# PSoC_PyunPyun_Mini.net
KiCad netlist of a schematic drawn in EAGLE
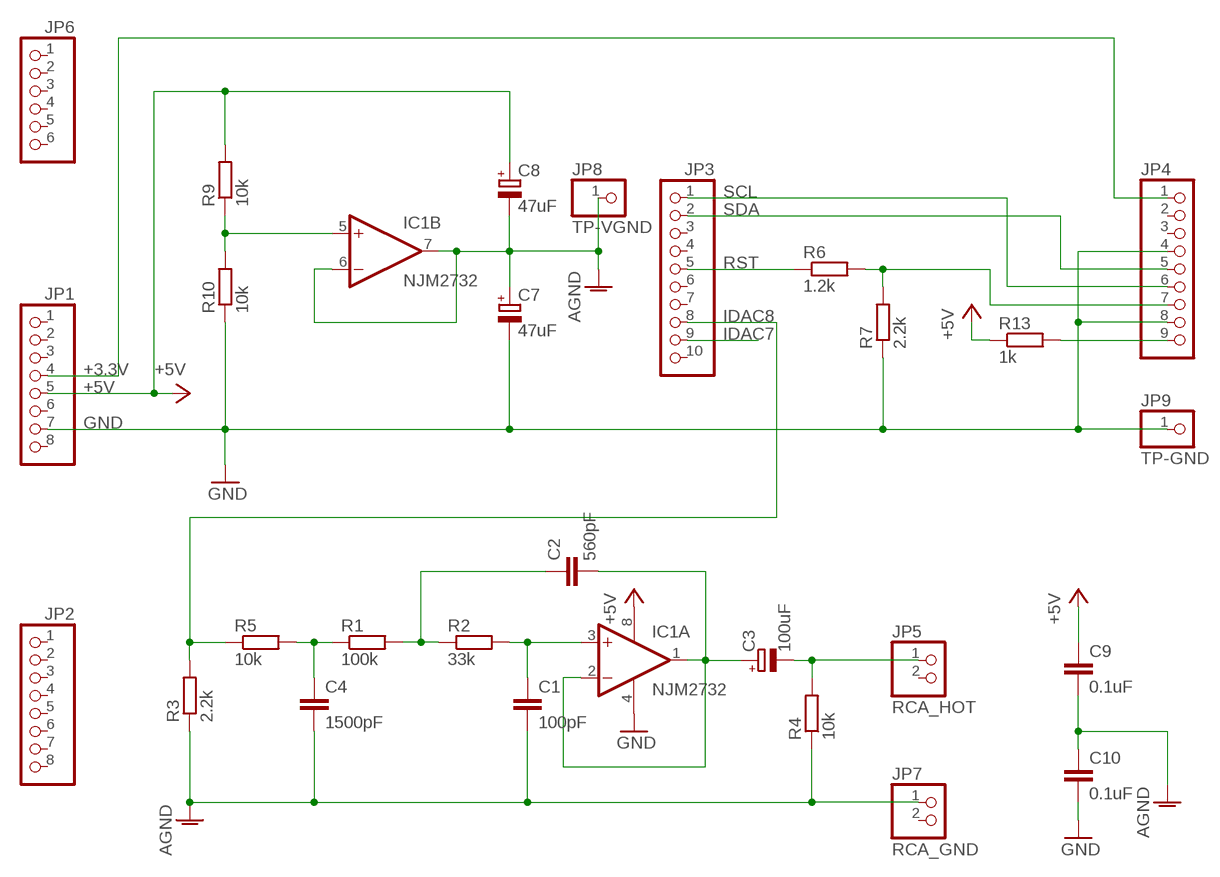
[diagram p0: schematic, sheet 1]

(export (version "E")
  (design (tool "Eeschema 10.0.6"))
  (components
    (comp (ref "C1")
      (value "100pF")
      (footprint "eagle-import:C050-024X044")
      (libsource (lib "eagle-import") (part "C-EU050-024X044"))
    )
    (comp (ref "C2")
      (value "560pF")
      (footprint "eagle-import:C050-024X044")
      (libsource (lib "eagle-import") (part "C-EU050-024X044"))
    )
    (comp (ref "C3")
      (value "100uF")
      (footprint "eagle-import:E2,5-7")
      (libsource (lib "eagle-import") (part "CPOL-EUE2.5-7"))
    )
    (comp (ref "C4")
      (value "1500pF")
      (footprint "eagle-import:C050-024X044")
      (libsource (lib "eagle-import") (part "C-EU050-024X044"))
    )
    (comp (ref "C7")
      (value "47uF")
      (footprint "eagle-import:E2,5-5")
      (libsource (lib "eagle-import") (part "CPOL-EUE2.5-5"))
    )
    (comp (ref "C8")
      (value "47uF")
      (footprint "eagle-import:E2,5-5")
      (libsource (lib "eagle-import") (part "CPOL-EUE2.5-5"))
    )
    (comp (ref "C9")
      (value "0.1uF")
      (footprint "eagle-import:C050-024X044")
      (libsource (lib "eagle-import") (part "C-EU050-024X044"))
    )
    (comp (ref "C10")
      (value "0.1uF")
      (footprint "eagle-import:C050-024X044")
      (libsource (lib "eagle-import") (part "C-EU050-024X044"))
    )
    (comp (ref "IC1")
      (value "NJM2732")
      (footprint "eagle-import:DIL08")
      (libsource (lib "eagle-import") (part "LM358N"))
    )
    (comp (ref "JP1")
      (value "PINHD-1X8")
      (footprint "eagle-import:1X08")
      (libsource (lib "eagle-import") (part "PINHD-1X8"))
    )
    (comp (ref "JP2")
      (value "PINHD-1X8")
      (footprint "eagle-import:1X08")
      (libsource (lib "eagle-import") (part "PINHD-1X8"))
    )
    (comp (ref "JP3")
      (value "PINHD-1X10")
      (footprint "eagle-import:1X10")
      (libsource (lib "eagle-import") (part "PINHD-1X10"))
    )
    (comp (ref "JP4")
      (value "PINHD-1X9")
      (footprint "eagle-import:1X09")
      (libsource (lib "eagle-import") (part "PINHD-1X9"))
    )
    (comp (ref "JP5")
      (value "RCA_HOT")
      (footprint "eagle-import:1X02")
      (libsource (lib "eagle-import") (part "PINHD-1X2"))
    )
    (comp (ref "JP6")
      (value "PINHD-1X6")
      (footprint "eagle-import:1X06")
      (libsource (lib "eagle-import") (part "PINHD-1X6"))
    )
    (comp (ref "JP7")
      (value "RCA_GND")
      (footprint "eagle-import:1X02")
      (libsource (lib "eagle-import") (part "PINHD-1X2"))
    )
    (comp (ref "JP8")
      (value "TP-VGND")
      (footprint "eagle-import:1X01")
      (libsource (lib "eagle-import") (part "PINHD-1X1"))
    )
    (comp (ref "JP9")
      (value "TP-GND")
      (footprint "eagle-import:1X01")
      (libsource (lib "eagle-import") (part "PINHD-1X1"))
    )
    (comp (ref "R1")
      (value "100k")
      (footprint "eagle-import:0207_7")
      (libsource (lib "eagle-import") (part "R-EU_0207/7"))
    )
    (comp (ref "R2")
      (value "33k")
      (footprint "eagle-import:0207_7")
      (libsource (lib "eagle-import") (part "R-EU_0207/7"))
    )
    (comp (ref "R3")
      (value "2.2k")
      (footprint "eagle-import:0207_7")
      (libsource (lib "eagle-import") (part "R-EU_0207/7"))
    )
    (comp (ref "R4")
      (value "10k")
      (footprint "eagle-import:0207_7")
      (libsource (lib "eagle-import") (part "R-EU_0207/7"))
    )
    (comp (ref "R5")
      (value "10k")
      (footprint "eagle-import:0207_7")
      (libsource (lib "eagle-import") (part "R-EU_0207/7"))
    )
    (comp (ref "R6")
      (value "1.2k")
      (footprint "eagle-import:0207_7")
      (libsource (lib "eagle-import") (part "R-EU_0207/7"))
    )
    (comp (ref "R7")
      (value "2.2k")
      (footprint "eagle-import:0207_7")
      (libsource (lib "eagle-import") (part "R-EU_0207/7"))
    )
    (comp (ref "R9")
      (value "10k")
      (footprint "eagle-import:0207_7")
      (libsource (lib "eagle-import") (part "R-EU_0207/7"))
    )
    (comp (ref "R10")
      (value "10k")
      (footprint "eagle-import:0207_7")
      (libsource (lib "eagle-import") (part "R-EU_0207/7"))
    )
    (comp (ref "R13")
      (value "1k")
      (footprint "eagle-import:0207_7")
      (libsource (lib "eagle-import") (part "R-EU_0207/7"))
    )
  )
  (nets
    (net (code "1") (name "+5V") (class "Default")
      (node (ref "C8") (pin "+") (pinfunction "+_+") (pintype "passive"))
      (node (ref "C9") (pin "1") (pinfunction "1_1") (pintype "passive"))
      (node (ref "IC1") (pin "8") (pinfunction "V+_8") (pintype "power_in"))
      (node (ref "JP1") (pin "5") (pinfunction "5_5") (pintype "passive"))
      (node (ref "R13") (pin "1") (pinfunction "1_1") (pintype "passive"))
      (node (ref "R9") (pin "2") (pinfunction "2_2") (pintype "passive"))
    )
    (net (code "2") (name "/+3.3V") (class "Default")
      (node (ref "JP1") (pin "4") (pinfunction "4_4") (pintype "passive"))
      (node (ref "JP4") (pin "1") (pinfunction "1_1") (pintype "passive"))
    )
    (net (code "3") (name "/IDAC7") (class "Default")
      (node (ref "JP3") (pin "9") (pinfunction "9_9") (pintype "passive"))
    )
    (net (code "4") (name "/IDAC8") (class "Default")
      (node (ref "JP3") (pin "8") (pinfunction "8_8") (pintype "passive"))
      (node (ref "R3") (pin "2") (pinfunction "2_2") (pintype "passive"))
      (node (ref "R5") (pin "1") (pinfunction "1_1") (pintype "passive"))
    )
    (net (code "5") (name "/RST") (class "Default")
      (node (ref "JP4") (pin "7") (pinfunction "7_7") (pintype "passive"))
      (node (ref "R6") (pin "2") (pinfunction "2_2") (pintype "passive"))
      (node (ref "R7") (pin "2") (pinfunction "2_2") (pintype "passive"))
    )
    (net (code "6") (name "/SCL") (class "Default")
      (node (ref "JP3") (pin "1") (pinfunction "1_1") (pintype "passive"))
      (node (ref "JP4") (pin "6") (pinfunction "6_6") (pintype "passive"))
    )
    (net (code "7") (name "/SDA") (class "Default")
      (node (ref "JP3") (pin "2") (pinfunction "2_2") (pintype "passive"))
      (node (ref "JP4") (pin "5") (pinfunction "5_5") (pintype "passive"))
    )
    (net (code "8") (name "AGND") (class "Default")
      (node (ref "C1") (pin "2") (pinfunction "2_2") (pintype "passive"))
      (node (ref "C10") (pin "1") (pinfunction "1_1") (pintype "passive"))
      (node (ref "C4") (pin "2") (pinfunction "2_2") (pintype "passive"))
      (node (ref "C7") (pin "+") (pinfunction "+_+") (pintype "passive"))
      (node (ref "C8") (pin "-") (pinfunction "-_-") (pintype "passive"))
      (node (ref "C9") (pin "2") (pinfunction "2_2") (pintype "passive"))
      (node (ref "IC1") (pin "6") (pinfunction "-IN_6") (pintype "input"))
      (node (ref "IC1") (pin "7") (pinfunction "OUT_7") (pintype "output"))
      (node (ref "JP7") (pin "1") (pinfunction "1_1") (pintype "passive"))
      (node (ref "JP8") (pin "1") (pinfunction "1_1") (pintype "passive"))
      (node (ref "R3") (pin "1") (pinfunction "1_1") (pintype "passive"))
      (node (ref "R4") (pin "1") (pinfunction "1_1") (pintype "passive"))
    )
    (net (code "9") (name "GND") (class "Default")
      (node (ref "C10") (pin "2") (pinfunction "2_2") (pintype "passive"))
      (node (ref "C7") (pin "-") (pinfunction "-_-") (pintype "passive"))
      (node (ref "IC1") (pin "4") (pinfunction "V-_4") (pintype "power_in"))
      (node (ref "JP1") (pin "7") (pinfunction "7_7") (pintype "passive"))
      (node (ref "JP4") (pin "4") (pinfunction "4_4") (pintype "passive"))
      (node (ref "JP4") (pin "8") (pinfunction "8_8") (pintype "passive"))
      (node (ref "JP9") (pin "1") (pinfunction "1_1") (pintype "passive"))
      (node (ref "R10") (pin "1") (pinfunction "1_1") (pintype "passive"))
      (node (ref "R7") (pin "1") (pinfunction "1_1") (pintype "passive"))
    )
    (net (code "10") (name "Net-(C2-Pad1)") (class "Default")
      (node (ref "C2") (pin "1") (pinfunction "1_1") (pintype "passive"))
      (node (ref "R1") (pin "2") (pinfunction "2_2") (pintype "passive"))
      (node (ref "R2") (pin "1") (pinfunction "1_1") (pintype "passive"))
    )
    (net (code "11") (name "Net-(C3-Pad-)") (class "Default")
      (node (ref "C3") (pin "-") (pinfunction "-_-") (pintype "passive"))
      (node (ref "JP5") (pin "1") (pinfunction "1_1") (pintype "passive"))
      (node (ref "R4") (pin "2") (pinfunction "2_2") (pintype "passive"))
    )
    (net (code "12") (name "Net-(C4-Pad1)") (class "Default")
      (node (ref "C4") (pin "1") (pinfunction "1_1") (pintype "passive"))
      (node (ref "R1") (pin "1") (pinfunction "1_1") (pintype "passive"))
      (node (ref "R5") (pin "2") (pinfunction "2_2") (pintype "passive"))
    )
    (net (code "13") (name "Net-(IC1A-+IN)") (class "Default")
      (node (ref "C1") (pin "1") (pinfunction "1_1") (pintype "passive"))
      (node (ref "IC1") (pin "3") (pinfunction "+IN_3") (pintype "input"))
      (node (ref "R2") (pin "2") (pinfunction "2_2") (pintype "passive"))
    )
    (net (code "14") (name "Net-(IC1A--IN)") (class "Default")
      (node (ref "C2") (pin "2") (pinfunction "2_2") (pintype "passive"))
      (node (ref "C3") (pin "+") (pinfunction "+_+") (pintype "passive"))
      (node (ref "IC1") (pin "1") (pinfunction "OUT_1") (pintype "output"))
      (node (ref "IC1") (pin "2") (pinfunction "-IN_2") (pintype "input"))
    )
    (net (code "15") (name "Net-(IC1B-+IN)") (class "Default")
      (node (ref "IC1") (pin "5") (pinfunction "+IN_5") (pintype "input"))
      (node (ref "R10") (pin "2") (pinfunction "2_2") (pintype "passive"))
      (node (ref "R9") (pin "1") (pinfunction "1_1") (pintype "passive"))
    )
    (net (code "16") (name "Net-(JP3-Pad5)") (class "Default")
      (node (ref "JP3") (pin "5") (pinfunction "5_5") (pintype "passive"))
      (node (ref "R6") (pin "1") (pinfunction "1_1") (pintype "passive"))
    )
    (net (code "17") (name "Net-(JP4-Pad9)") (class "Default")
      (node (ref "JP4") (pin "9") (pinfunction "9_9") (pintype "passive"))
      (node (ref "R13") (pin "2") (pinfunction "2_2") (pintype "passive"))
    )
    (net (code "18") (name "unconnected-(JP1-Pad1)") (class "Default")
      (node (ref "JP1") (pin "1") (pinfunction "1_1") (pintype "passive"))
    )
    (net (code "19") (name "unconnected-(JP1-Pad2)") (class "Default")
      (node (ref "JP1") (pin "2") (pinfunction "2_2") (pintype "passive"))
    )
    (net (code "20") (name "unconnected-(JP1-Pad3)") (class "Default")
      (node (ref "JP1") (pin "3") (pinfunction "3_3") (pintype "passive"))
    )
    (net (code "21") (name "unconnected-(JP1-Pad6)") (class "Default")
      (node (ref "JP1") (pin "6") (pinfunction "6_6") (pintype "passive"))
    )
    (net (code "22") (name "unconnected-(JP1-Pad8)") (class "Default")
      (node (ref "JP1") (pin "8") (pinfunction "8_8") (pintype "passive"))
    )
    (net (code "23") (name "unconnected-(JP2-Pad1)") (class "Default")
      (node (ref "JP2") (pin "1") (pinfunction "1_1") (pintype "passive"))
    )
    (net (code "24") (name "unconnected-(JP2-Pad2)") (class "Default")
      (node (ref "JP2") (pin "2") (pinfunction "2_2") (pintype "passive"))
    )
    (net (code "25") (name "unconnected-(JP2-Pad3)") (class "Default")
      (node (ref "JP2") (pin "3") (pinfunction "3_3") (pintype "passive"))
    )
    (net (code "26") (name "unconnected-(JP2-Pad4)") (class "Default")
      (node (ref "JP2") (pin "4") (pinfunction "4_4") (pintype "passive"))
    )
    (net (code "27") (name "unconnected-(JP2-Pad5)") (class "Default")
      (node (ref "JP2") (pin "5") (pinfunction "5_5") (pintype "passive"))
    )
    (net (code "28") (name "unconnected-(JP2-Pad6)") (class "Default")
      (node (ref "JP2") (pin "6") (pinfunction "6_6") (pintype "passive"))
    )
    (net (code "29") (name "unconnected-(JP2-Pad7)") (class "Default")
      (node (ref "JP2") (pin "7") (pinfunction "7_7") (pintype "passive"))
    )
    (net (code "30") (name "unconnected-(JP2-Pad8)") (class "Default")
      (node (ref "JP2") (pin "8") (pinfunction "8_8") (pintype "passive"))
    )
    (net (code "31") (name "unconnected-(JP3-Pad3)") (class "Default")
      (node (ref "JP3") (pin "3") (pinfunction "3_3") (pintype "passive"))
    )
    (net (code "32") (name "unconnected-(JP3-Pad4)") (class "Default")
      (node (ref "JP3") (pin "4") (pinfunction "4_4") (pintype "passive"))
    )
    (net (code "33") (name "unconnected-(JP3-Pad6)") (class "Default")
      (node (ref "JP3") (pin "6") (pinfunction "6_6") (pintype "passive"))
    )
    (net (code "34") (name "unconnected-(JP3-Pad7)") (class "Default")
      (node (ref "JP3") (pin "7") (pinfunction "7_7") (pintype "passive"))
    )
    (net (code "35") (name "unconnected-(JP3-Pad10)") (class "Default")
      (node (ref "JP3") (pin "10") (pinfunction "10_10") (pintype "passive"))
    )
    (net (code "36") (name "unconnected-(JP4-Pad2)") (class "Default")
      (node (ref "JP4") (pin "2") (pinfunction "2_2") (pintype "passive"))
    )
    (net (code "37") (name "unconnected-(JP4-Pad3)") (class "Default")
      (node (ref "JP4") (pin "3") (pinfunction "3_3") (pintype "passive"))
    )
    (net (code "38") (name "unconnected-(JP5-Pad2)") (class "Default")
      (node (ref "JP5") (pin "2") (pinfunction "2_2") (pintype "passive"))
    )
    (net (code "39") (name "unconnected-(JP6-Pad1)") (class "Default")
      (node (ref "JP6") (pin "1") (pinfunction "1_1") (pintype "passive"))
    )
    (net (code "40") (name "unconnected-(JP6-Pad2)") (class "Default")
      (node (ref "JP6") (pin "2") (pinfunction "2_2") (pintype "passive"))
    )
    (net (code "41") (name "unconnected-(JP6-Pad3)") (class "Default")
      (node (ref "JP6") (pin "3") (pinfunction "3_3") (pintype "passive"))
    )
    (net (code "42") (name "unconnected-(JP6-Pad4)") (class "Default")
      (node (ref "JP6") (pin "4") (pinfunction "4_4") (pintype "passive"))
    )
    (net (code "43") (name "unconnected-(JP6-Pad5)") (class "Default")
      (node (ref "JP6") (pin "5") (pinfunction "5_5") (pintype "passive"))
    )
    (net (code "44") (name "unconnected-(JP6-Pad6)") (class "Default")
      (node (ref "JP6") (pin "6") (pinfunction "6_6") (pintype "passive"))
    )
    (net (code "45") (name "unconnected-(JP7-Pad2)") (class "Default")
      (node (ref "JP7") (pin "2") (pinfunction "2_2") (pintype "passive"))
    )
  )
)
